# MicrowaveOvenControl.net
KiCad netlist of a schematic drawn in EasyEDA Pro
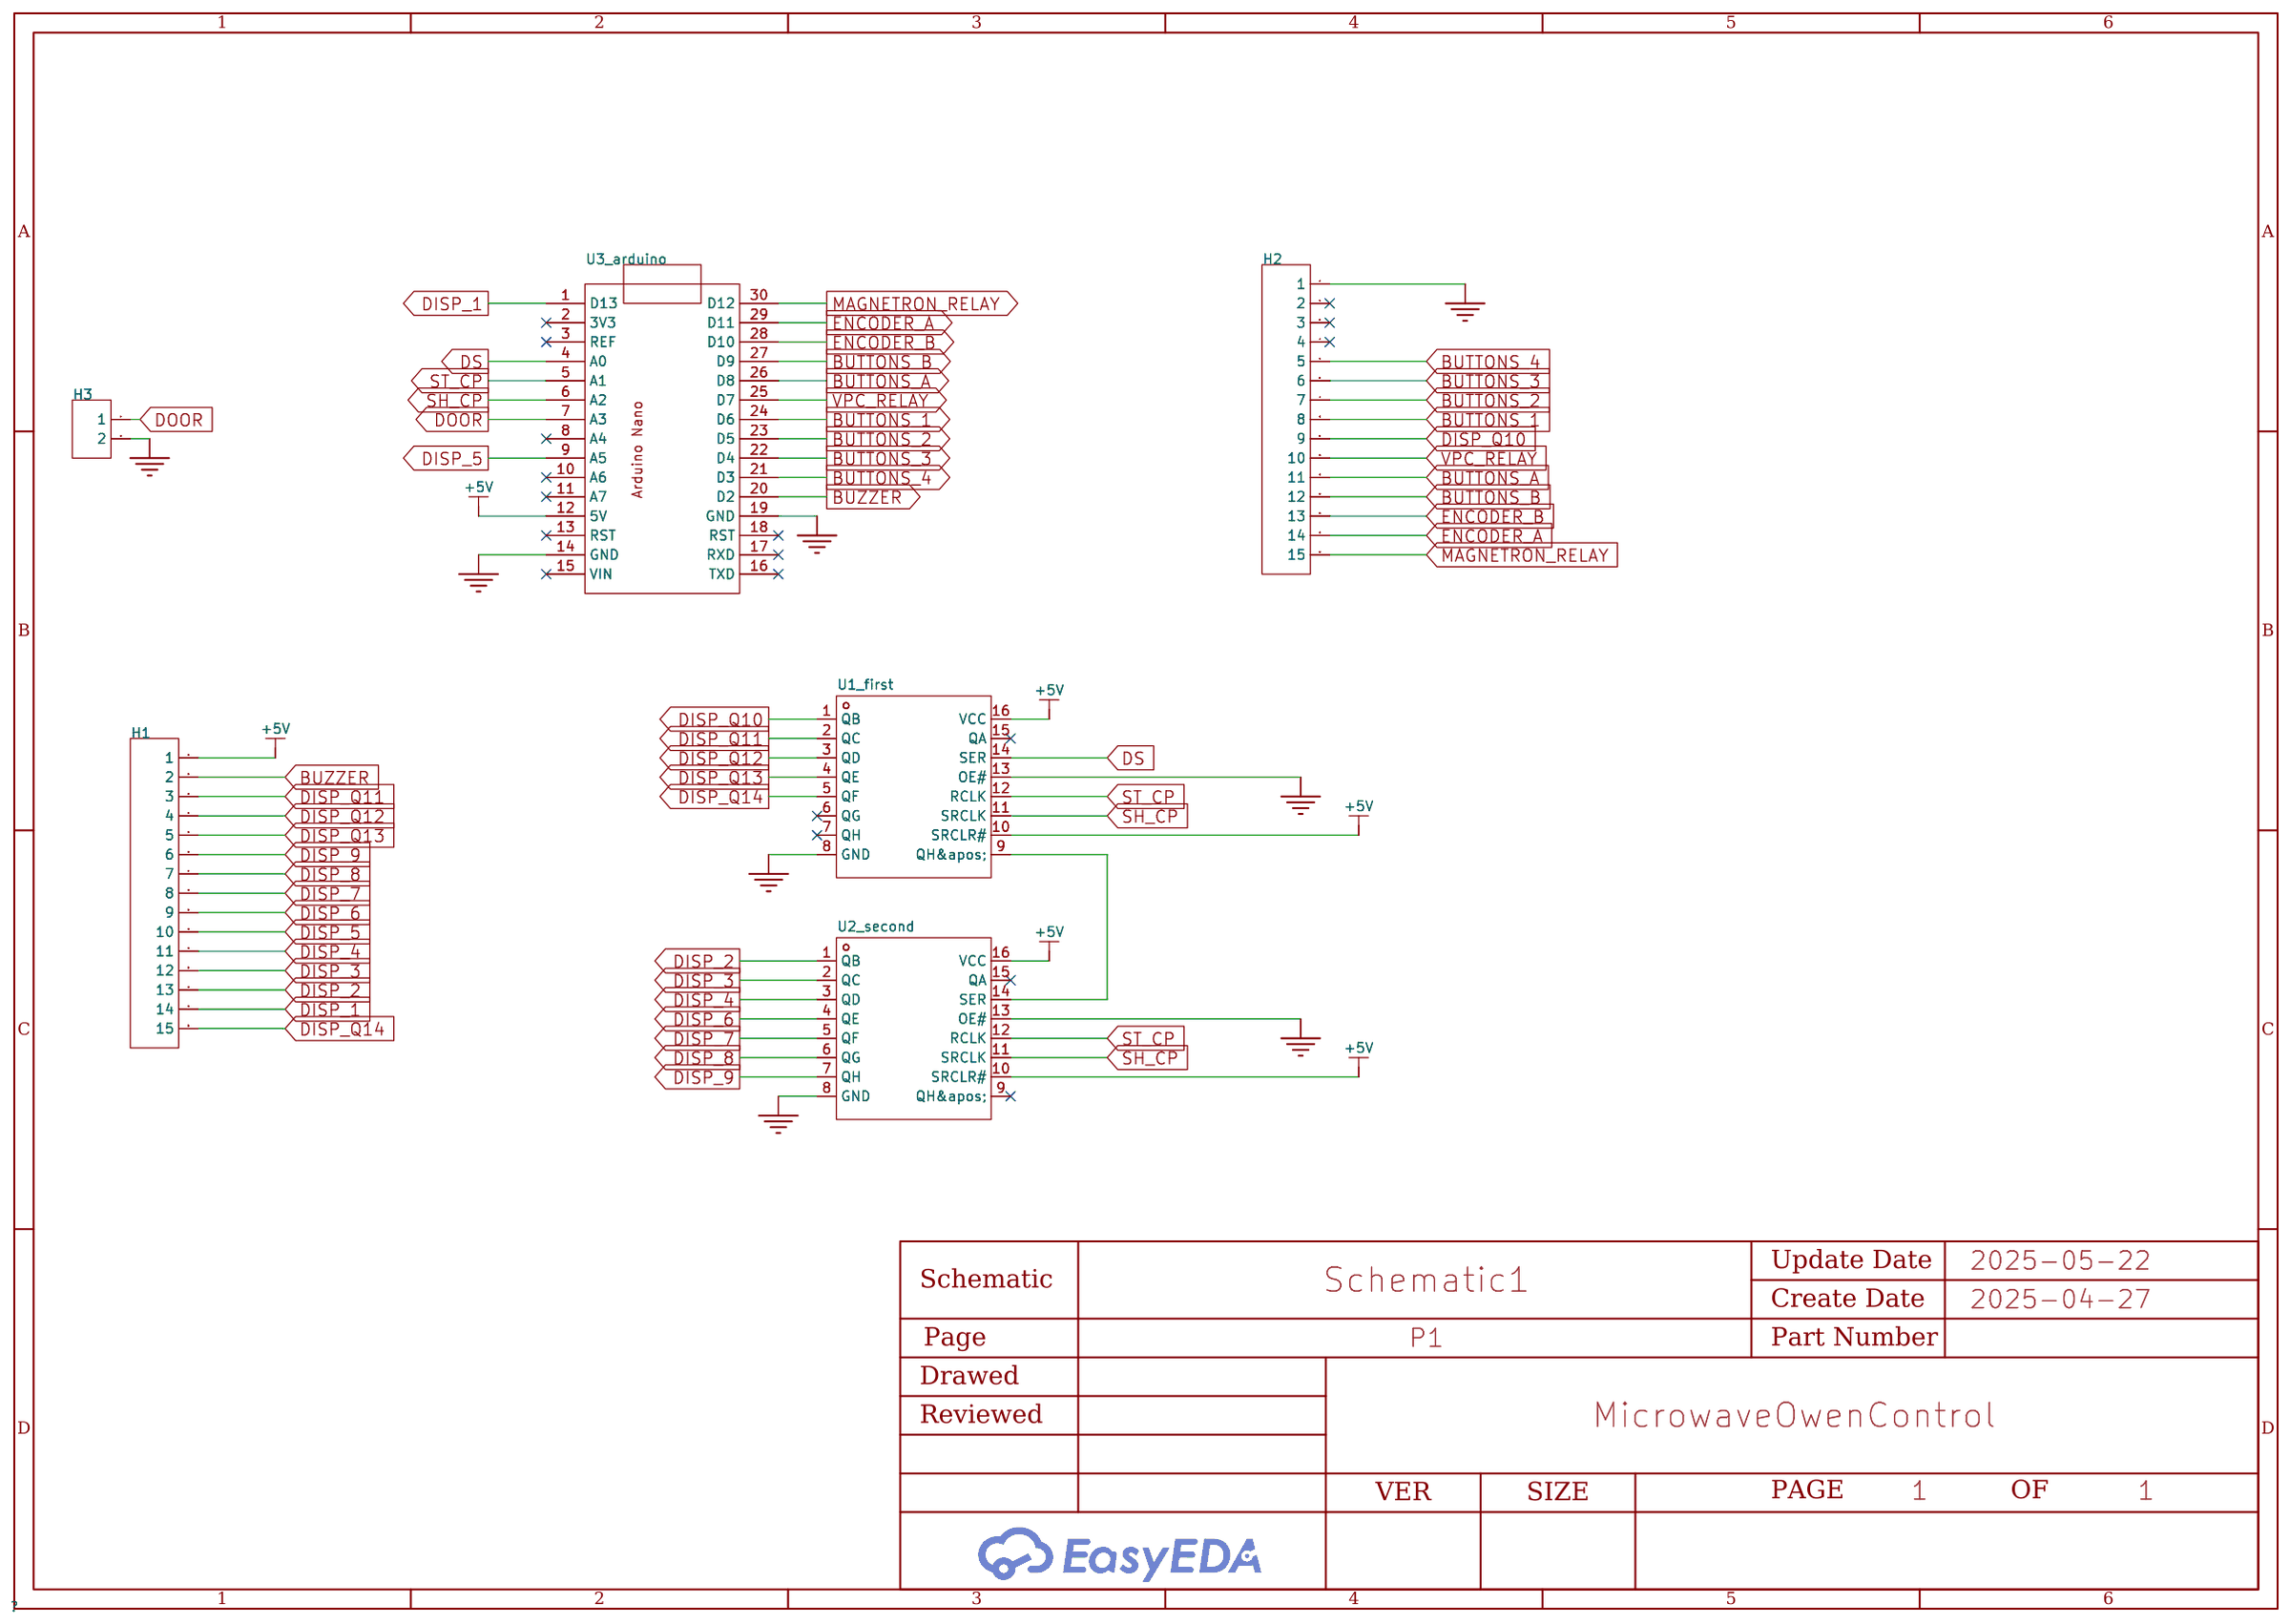
[diagram p0: schematic sheet]

(export (version "E")
  (design (tool "Eeschema 10.0.6"))
  (components
    (comp (ref "H1")
      (value "~")
      (footprint "easyedapro:HDR-TH_15P-P2.54-V-F-1")
      (libsource (lib "easyedapro") (part "HDR-F_2.54_1x15P"))
    )
    (comp (ref "H2")
      (value "~")
      (footprint "easyedapro:HDR-TH_15P-P2.54-V-F-1")
      (libsource (lib "easyedapro") (part "HDR-F_2.54_1x15P"))
    )
    (comp (ref "H3")
      (value "~")
      (footprint "easyedapro:HDR-TH_2P-P2.54-V-F")
      (libsource (lib "easyedapro") (part "Header-Female-2.54_1x2"))
    )
    (comp (ref "U1_first")
      (value "~")
      (footprint "easyedapro:DIP-16_L19.8-W6.5-P2.54-LS7.6-BL")
      (fields (field (name "Manufacturer Part") "SN74HC595N") (field (name "Manufacturer") "TI(德州仪器)"))
      (libsource (lib "easyedapro") (part "SN74HC595N"))
    )
    (comp (ref "U2_second")
      (value "~")
      (footprint "easyedapro:DIP-16_L19.8-W6.5-P2.54-LS7.6-BL")
      (fields (field (name "Manufacturer Part") "SN74HC595N") (field (name "Manufacturer") "TI(德州仪器)"))
      (libsource (lib "easyedapro") (part "SN74HC595N"))
    )
    (comp (ref "U3_arduino")
      (value "~")
      (footprint "easyedapro:ArduinoNanoFootprint")
      (libsource (lib "easyedapro") (part "ArduinoNano"))
    )
  )
  (nets
    (net (code "1") (name "+5V") (class "Default")
      (node (ref "H1") (pin "1") (pinfunction "1_1") (pintype "input"))
      (node (ref "U1_first") (pin "10") (pinfunction "SRCLR#_10") (pintype "input"))
      (node (ref "U1_first") (pin "16") (pinfunction "VCC_16") (pintype "input"))
      (node (ref "U2_second") (pin "10") (pinfunction "SRCLR#_10") (pintype "input"))
      (node (ref "U2_second") (pin "16") (pinfunction "VCC_16") (pintype "input"))
      (node (ref "U3_arduino") (pin "12") (pinfunction "5V_12") (pintype "input"))
    )
    (net (code "2") (name "BUTTONS_1") (class "Default")
      (node (ref "H2") (pin "8") (pinfunction "8_8") (pintype "input"))
      (node (ref "U3_arduino") (pin "24") (pinfunction "D6_24") (pintype "input"))
    )
    (net (code "3") (name "BUTTONS_2") (class "Default")
      (node (ref "H2") (pin "7") (pinfunction "7_7") (pintype "input"))
      (node (ref "U3_arduino") (pin "23") (pinfunction "D5_23") (pintype "input"))
    )
    (net (code "4") (name "BUTTONS_3") (class "Default")
      (node (ref "H2") (pin "6") (pinfunction "6_6") (pintype "input"))
      (node (ref "U3_arduino") (pin "22") (pinfunction "D4_22") (pintype "input"))
    )
    (net (code "5") (name "BUTTONS_4") (class "Default")
      (node (ref "H2") (pin "5") (pinfunction "5_5") (pintype "input"))
      (node (ref "U3_arduino") (pin "21") (pinfunction "D3_21") (pintype "input"))
    )
    (net (code "6") (name "BUTTONS_A") (class "Default")
      (node (ref "H2") (pin "11") (pinfunction "11_11") (pintype "input"))
      (node (ref "U3_arduino") (pin "26") (pinfunction "D8_26") (pintype "input"))
    )
    (net (code "7") (name "BUTTONS_B") (class "Default")
      (node (ref "H2") (pin "12") (pinfunction "12_12") (pintype "input"))
      (node (ref "U3_arduino") (pin "27") (pinfunction "D9_27") (pintype "input"))
    )
    (net (code "8") (name "BUZZER") (class "Default")
      (node (ref "H1") (pin "2") (pinfunction "2_2") (pintype "input"))
      (node (ref "U3_arduino") (pin "20") (pinfunction "D2_20") (pintype "input"))
    )
    (net (code "9") (name "DISP_1") (class "Default")
      (node (ref "H1") (pin "14") (pinfunction "14_14") (pintype "input"))
      (node (ref "U3_arduino") (pin "1") (pinfunction "D13_1") (pintype "input"))
    )
    (net (code "10") (name "DISP_2") (class "Default")
      (node (ref "H1") (pin "13") (pinfunction "13_13") (pintype "input"))
      (node (ref "U2_second") (pin "1") (pinfunction "QB_1") (pintype "input"))
    )
    (net (code "11") (name "DISP_3") (class "Default")
      (node (ref "H1") (pin "12") (pinfunction "12_12") (pintype "input"))
      (node (ref "U2_second") (pin "2") (pinfunction "QC_2") (pintype "input"))
    )
    (net (code "12") (name "DISP_4") (class "Default")
      (node (ref "H1") (pin "11") (pinfunction "11_11") (pintype "input"))
      (node (ref "U2_second") (pin "3") (pinfunction "QD_3") (pintype "input"))
    )
    (net (code "13") (name "DISP_5") (class "Default")
      (node (ref "H1") (pin "10") (pinfunction "10_10") (pintype "input"))
      (node (ref "U3_arduino") (pin "9") (pinfunction "A5_9") (pintype "input"))
    )
    (net (code "14") (name "DISP_6") (class "Default")
      (node (ref "H1") (pin "9") (pinfunction "9_9") (pintype "input"))
      (node (ref "U2_second") (pin "4") (pinfunction "QE_4") (pintype "input"))
    )
    (net (code "15") (name "DISP_7") (class "Default")
      (node (ref "H1") (pin "8") (pinfunction "8_8") (pintype "input"))
      (node (ref "U2_second") (pin "5") (pinfunction "QF_5") (pintype "input"))
    )
    (net (code "16") (name "DISP_8") (class "Default")
      (node (ref "H1") (pin "7") (pinfunction "7_7") (pintype "input"))
      (node (ref "U2_second") (pin "6") (pinfunction "QG_6") (pintype "input"))
    )
    (net (code "17") (name "DISP_9") (class "Default")
      (node (ref "H1") (pin "6") (pinfunction "6_6") (pintype "input"))
      (node (ref "U2_second") (pin "7") (pinfunction "QH_7") (pintype "input"))
    )
    (net (code "18") (name "DISP_Q10") (class "Default")
      (node (ref "H2") (pin "9") (pinfunction "9_9") (pintype "input"))
      (node (ref "U1_first") (pin "1") (pinfunction "QB_1") (pintype "input"))
    )
    (net (code "19") (name "DISP_Q11") (class "Default")
      (node (ref "H1") (pin "3") (pinfunction "3_3") (pintype "input"))
      (node (ref "U1_first") (pin "2") (pinfunction "QC_2") (pintype "input"))
    )
    (net (code "20") (name "DISP_Q12") (class "Default")
      (node (ref "H1") (pin "4") (pinfunction "4_4") (pintype "input"))
      (node (ref "U1_first") (pin "3") (pinfunction "QD_3") (pintype "input"))
    )
    (net (code "21") (name "DISP_Q13") (class "Default")
      (node (ref "H1") (pin "5") (pinfunction "5_5") (pintype "input"))
      (node (ref "U1_first") (pin "4") (pinfunction "QE_4") (pintype "input"))
    )
    (net (code "22") (name "DISP_Q14") (class "Default")
      (node (ref "H1") (pin "15") (pinfunction "15_15") (pintype "input"))
      (node (ref "U1_first") (pin "5") (pinfunction "QF_5") (pintype "input"))
    )
    (net (code "23") (name "DOOR") (class "Default")
      (node (ref "H3") (pin "1") (pinfunction "1_1") (pintype "input"))
      (node (ref "U3_arduino") (pin "7") (pinfunction "A3_7") (pintype "input"))
    )
    (net (code "24") (name "DS") (class "Default")
      (node (ref "U1_first") (pin "14") (pinfunction "SER_14") (pintype "input"))
      (node (ref "U3_arduino") (pin "4") (pinfunction "A0_4") (pintype "input"))
    )
    (net (code "25") (name "ENCODER_A") (class "Default")
      (node (ref "H2") (pin "14") (pinfunction "14_14") (pintype "input"))
      (node (ref "U3_arduino") (pin "29") (pinfunction "D11_29") (pintype "input"))
    )
    (net (code "26") (name "ENCODER_B") (class "Default")
      (node (ref "H2") (pin "13") (pinfunction "13_13") (pintype "input"))
      (node (ref "U3_arduino") (pin "28") (pinfunction "D10_28") (pintype "input"))
    )
    (net (code "27") (name "GND") (class "Default")
      (node (ref "H2") (pin "1") (pinfunction "1_1") (pintype "input"))
      (node (ref "H3") (pin "2") (pinfunction "2_2") (pintype "input"))
      (node (ref "U1_first") (pin "13") (pinfunction "OE#_13") (pintype "input"))
      (node (ref "U1_first") (pin "8") (pinfunction "GND_8") (pintype "input"))
      (node (ref "U2_second") (pin "13") (pinfunction "OE#_13") (pintype "input"))
      (node (ref "U2_second") (pin "8") (pinfunction "GND_8") (pintype "input"))
      (node (ref "U3_arduino") (pin "14") (pinfunction "GND_14") (pintype "input"))
      (node (ref "U3_arduino") (pin "19") (pinfunction "GND_19") (pintype "input"))
    )
    (net (code "28") (name "MAGNETRON_RELAY") (class "Default")
      (node (ref "H2") (pin "15") (pinfunction "15_15") (pintype "input"))
      (node (ref "U3_arduino") (pin "30") (pinfunction "D12_30") (pintype "input"))
    )
    (net (code "29") (name "Net-(U1_first-QH&apos;)") (class "Default")
      (node (ref "U1_first") (pin "9") (pinfunction "QH&apos;_9") (pintype "input"))
      (node (ref "U2_second") (pin "14") (pinfunction "SER_14") (pintype "input"))
    )
    (net (code "30") (name "SH_CP") (class "Default")
      (node (ref "U1_first") (pin "11") (pinfunction "SRCLK_11") (pintype "input"))
      (node (ref "U2_second") (pin "11") (pinfunction "SRCLK_11") (pintype "input"))
      (node (ref "U3_arduino") (pin "6") (pinfunction "A2_6") (pintype "input"))
    )
    (net (code "31") (name "ST_CP") (class "Default")
      (node (ref "U1_first") (pin "12") (pinfunction "RCLK_12") (pintype "input"))
      (node (ref "U2_second") (pin "12") (pinfunction "RCLK_12") (pintype "input"))
      (node (ref "U3_arduino") (pin "5") (pinfunction "A1_5") (pintype "input"))
    )
    (net (code "32") (name "VPC_RELAY") (class "Default")
      (node (ref "H2") (pin "10") (pinfunction "10_10") (pintype "input"))
      (node (ref "U3_arduino") (pin "25") (pinfunction "D7_25") (pintype "input"))
    )
    (net (code "33") (name "unconnected-(H2-Pad2)") (class "Default")
      (node (ref "H2") (pin "2") (pinfunction "2_2") (pintype "input+no_connect"))
    )
    (net (code "34") (name "unconnected-(H2-Pad3)") (class "Default")
      (node (ref "H2") (pin "3") (pinfunction "3_3") (pintype "input+no_connect"))
    )
    (net (code "35") (name "unconnected-(H2-Pad4)") (class "Default")
      (node (ref "H2") (pin "4") (pinfunction "4_4") (pintype "input+no_connect"))
    )
    (net (code "36") (name "unconnected-(U1_first-QA-Pad15)") (class "Default")
      (node (ref "U1_first") (pin "15") (pinfunction "QA_15") (pintype "input+no_connect"))
    )
    (net (code "37") (name "unconnected-(U1_first-QG-Pad6)") (class "Default")
      (node (ref "U1_first") (pin "6") (pinfunction "QG_6") (pintype "input+no_connect"))
    )
    (net (code "38") (name "unconnected-(U1_first-QH-Pad7)") (class "Default")
      (node (ref "U1_first") (pin "7") (pinfunction "QH_7") (pintype "input+no_connect"))
    )
    (net (code "39") (name "unconnected-(U2_second-QA-Pad15)") (class "Default")
      (node (ref "U2_second") (pin "15") (pinfunction "QA_15") (pintype "input+no_connect"))
    )
    (net (code "40") (name "unconnected-(U2_second-QH&apos;-Pad9)") (class "Default")
      (node (ref "U2_second") (pin "9") (pinfunction "QH&apos;_9") (pintype "input+no_connect"))
    )
    (net (code "41") (name "unconnected-(U3_arduino-3V3-Pad2)") (class "Default")
      (node (ref "U3_arduino") (pin "2") (pinfunction "3V3_2") (pintype "input+no_connect"))
    )
    (net (code "42") (name "unconnected-(U3_arduino-A4-Pad8)") (class "Default")
      (node (ref "U3_arduino") (pin "8") (pinfunction "A4_8") (pintype "input+no_connect"))
    )
    (net (code "43") (name "unconnected-(U3_arduino-A6-Pad10)") (class "Default")
      (node (ref "U3_arduino") (pin "10") (pinfunction "A6_10") (pintype "input+no_connect"))
    )
    (net (code "44") (name "unconnected-(U3_arduino-A7-Pad11)") (class "Default")
      (node (ref "U3_arduino") (pin "11") (pinfunction "A7_11") (pintype "input+no_connect"))
    )
    (net (code "45") (name "unconnected-(U3_arduino-REF-Pad3)") (class "Default")
      (node (ref "U3_arduino") (pin "3") (pinfunction "REF_3") (pintype "input+no_connect"))
    )
    (net (code "46") (name "unconnected-(U3_arduino-RST-Pad13)") (class "Default")
      (node (ref "U3_arduino") (pin "13") (pinfunction "RST_13") (pintype "input+no_connect"))
    )
    (net (code "47") (name "unconnected-(U3_arduino-RST-Pad18)") (class "Default")
      (node (ref "U3_arduino") (pin "18") (pinfunction "RST_18") (pintype "input+no_connect"))
    )
    (net (code "48") (name "unconnected-(U3_arduino-RXD-Pad17)") (class "Default")
      (node (ref "U3_arduino") (pin "17") (pinfunction "RXD_17") (pintype "input+no_connect"))
    )
    (net (code "49") (name "unconnected-(U3_arduino-TXD-Pad16)") (class "Default")
      (node (ref "U3_arduino") (pin "16") (pinfunction "TXD_16") (pintype "input+no_connect"))
    )
    (net (code "50") (name "unconnected-(U3_arduino-VIN-Pad15)") (class "Default")
      (node (ref "U3_arduino") (pin "15") (pinfunction "VIN_15") (pintype "input+no_connect"))
    )
  )
)
